# Boost_Converter_1.net
KiCad netlist of a schematic drawn in Altium Designer
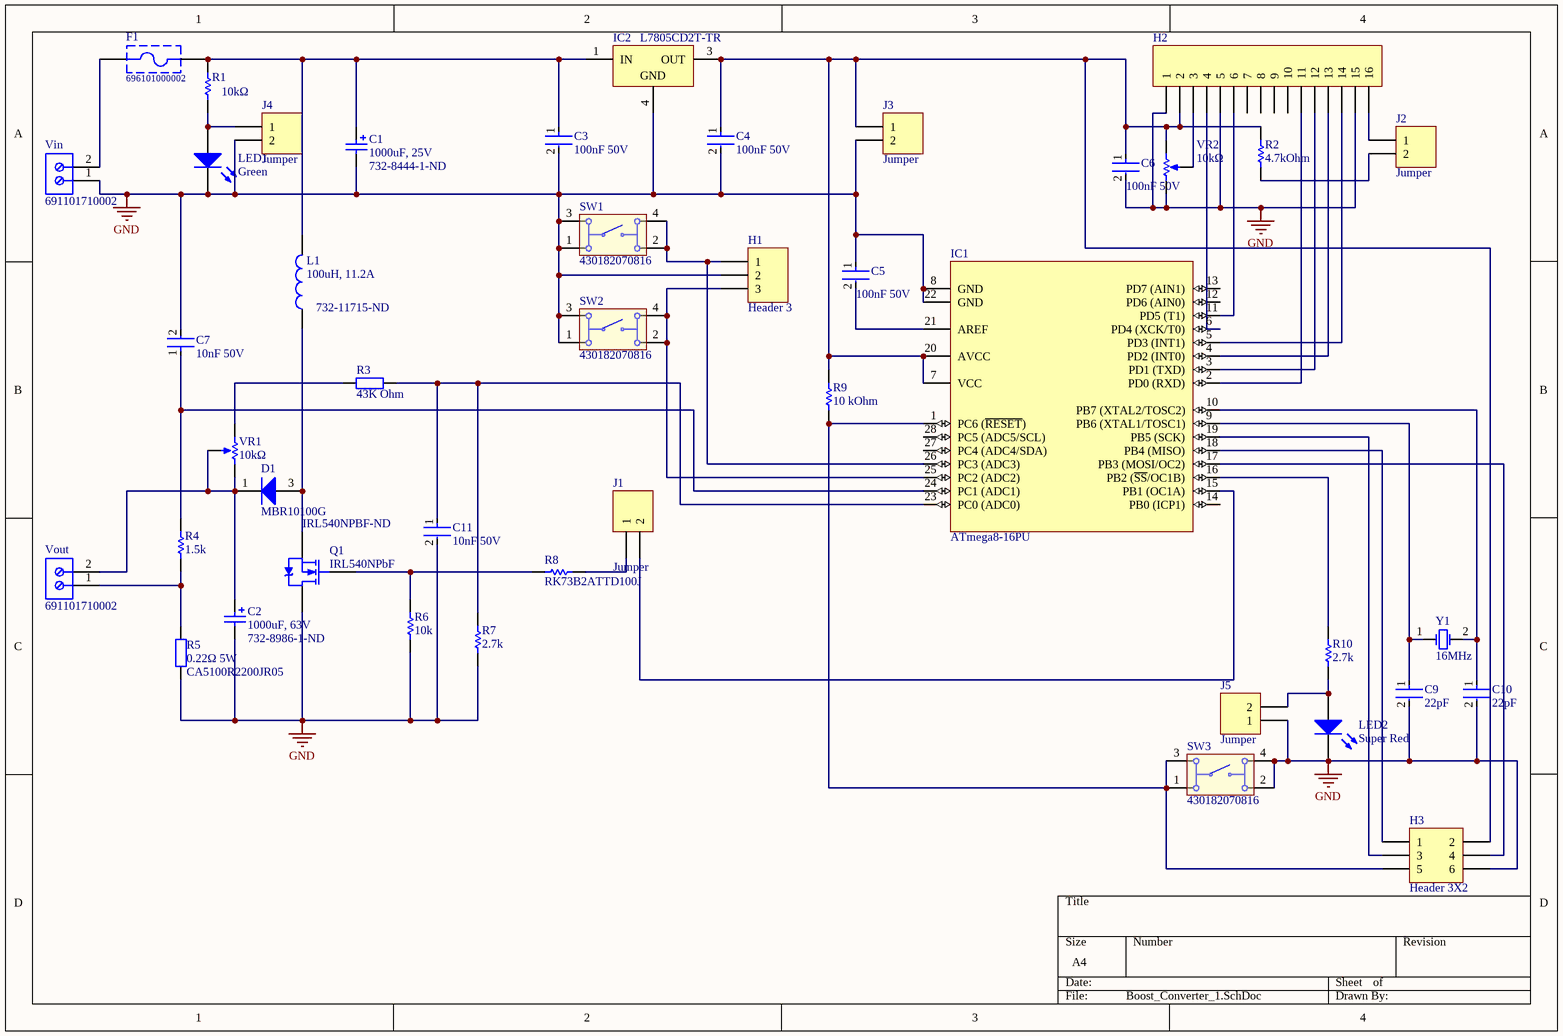
[diagram p0: Boost_Converter_1.SchDoc]

(export (version "E")
  (design (tool "Eeschema 10.0.6"))
  (components
    (comp (ref "C1")
      (value "1000uF, 25V")
      (footprint "WCAP-ASLI_D12.5H14")
      (description "WCAP-ASLI Aluminum Electrolytic Capacitor, V-Chip, SMT, D12.5xH14mm, 1000uF, 25V")
      (fields
        (field (name "MANUFACTURER PART NUMBER") "865080462016")
        (field (name "MANUFACTURER") "Wurth Elektronik")
        (field (name "SUPPLIER PART NUMBER 1") "732-8444-1-ND")
      )
      (libsource (lib "Altium_WCAP-ASLI (rev20b)") (part "865080462016"))
    )
    (comp (ref "C2")
      (value "1000uF, 63V")
      (footprint "WCAP-ATG5_D16H31.5")
      (description "CAP ALUM 1000UF 20% 63V RADIAL")
      (fields
        (field (name "MANUFACTURER PART NUMBER") "860020780025")
        (field (name "MANUFACTURER") "Wurth Elektronik")
        (field (name "SUPPLIER PART NUMBER 1") "732-8986-1-ND")
      )
      (libsource (lib "Altium_WCAP-ATG5 (rev20b)") (part "860020780025"))
    )
    (comp (ref "C3")
      (value "100nF 50V")
      (footprint "FP-GCD21B-0_15-IPC_C")
      (description "Chip Multilayer Ceramic Capacitors for Automotive, 0805, 0.10uF, X7R, 15%, 10%, 50V, Grade 1")
      (fields (field (name "TOLERANCE") "10%"))
      (libsource (lib "Altium Content Vault") (part "b4654b650e69147ec39a6b967a45e02"))
    )
    (comp (ref "C4")
      (value "100nF 50V")
      (footprint "FP-GCD21B-0_15-IPC_C")
      (description "Chip Multilayer Ceramic Capacitors for Automotive, 0805, 0.10uF, X7R, 15%, 10%, 50V, Grade 1")
      (fields (field (name "TOLERANCE") "10%"))
      (libsource (lib "Altium Content Vault") (part "b4654b650e69147ec39a6b967a45e02"))
    )
    (comp (ref "C5")
      (value "100nF 50V")
      (footprint "FP-CL31-IPC_C")
      (description "Cap Ceramic 100nF 50V X7R ±10% SMD 1206 +125°C Embossed T/R")
      (fields (field (name "VOLTAGE") "50V") (field (name "TOLERANCE") "10%"))
      (libsource (lib "Altium Content Vault") (part "b4654b650e69147ec39a6b967a45e02"))
    )
    (comp (ref "C6")
      (value "100nF 50V")
      (footprint "FP-CL31-IPC_C")
      (description "Cap Ceramic 100nF 50V X7R ±10% SMD 1206 +125°C Embossed T/R")
      (fields (field (name "VOLTAGE") "50V") (field (name "TOLERANCE") "10%"))
      (libsource (lib "Altium Content Vault") (part "b4654b650e69147ec39a6b967a45e02"))
    )
    (comp (ref "C7")
      (value "10nF 50V")
      (footprint "FP-CL21-IPC_C")
      (description "CL21 Series 0805 10nF 50V ±10% Tolerance X7R Multilayer Ceramic Chip Capacitor")
      (fields (field (name "TOLERANCE") "10%"))
      (libsource (lib "Altium Content Vault") (part "b4654b650e69147ec39a6b967a45e02"))
    )
    (comp (ref "C9")
      (value "22pF")
      (footprint "FP-C0805C-DN-MFG")
      (description "CAP CER 22PF 50V C0G/NP0 0805")
      (fields
        (field (name "OCTOPART") "https://octopart.com/c0805c220j5gac7210-kemet-3882539")
        (field (name "MANUFACTURER PART NUMBER") "C0805C220J5GAC7210")
      )
      (libsource (lib "Altium Content Vault") (part "b4654b650e69147ec39a6b967a45e02"))
    )
    (comp (ref "C10")
      (value "22pF")
      (footprint "FP-C0805C-DN-MFG")
      (description "CAP CER 22PF 50V C0G/NP0 0805")
      (fields
        (field (name "OCTOPART") "https://octopart.com/c0805c220j5gac7210-kemet-3882539")
        (field (name "MANUFACTURER PART NUMBER") "C0805C220J5GAC7210")
      )
      (libsource (lib "Altium Content Vault") (part "b4654b650e69147ec39a6b967a45e02"))
    )
    (comp (ref "C11")
      (value "10nF 50V")
      (footprint "FP-CL21-IPC_C")
      (description "CL21 Series 0805 10nF 50V ±10% Tolerance X7R Multilayer Ceramic Chip Capacitor")
      (fields (field (name "TOLERANCE") "10%"))
      (libsource (lib "Altium Content Vault") (part "b4654b650e69147ec39a6b967a45e02"))
    )
    (comp (ref "D1")
      (value "MBR10100G")
      (footprint "ONSC-TO-220-2-221B-04_E")
      (description "SWITCHMODE(TM) Power Rectifier, 2-Pin TO-220, Pb-Free, Tube")
      (fields (field (name "MANUFACTURER") "On Semiconductor"))
      (libsource (lib "Altium Content Vault") (part "ONSC-D-K1A3-2_A"))
    )
    (comp (ref "F1")
      (value "696101000002")
      (footprint "696101000002")
      (description "WR-FSH Fuse Holder Blocks Fuse Holder Blocks Clip Cover for PCB")
      (fields (field (name "PUBLISHER") "Wurth Elektronik"))
      (libsource (lib "Altium_WR-FSH (rev18a)") (part "696101000002"))
    )
    (comp (ref "H1")
      (value "Header 3")
      (footprint "HDR1X3")
      (description "Header, 3-Pin")
      (fields (field (name "PUBLISHER") "Altium Limited"))
      (libsource (lib "Miscellaneous Connectors") (part "Header 3"))
    )
    (comp (ref "H2")
      (value "Header 16")
      (footprint "HDR1X16")
      (description "Header, 16-Pin")
      (fields (field (name "PUBLISHER") "Altium Limited"))
      (libsource (lib "Miscellaneous Connectors") (part "Header 16"))
    )
    (comp (ref "H3")
      (value "Header 3X2")
      (footprint "HDR2X3")
      (description "Header, 3-Pin, Dual row")
      (fields (field (name "PUBLISHER") "Altium Limited"))
      (libsource (lib "Miscellaneous Connectors") (part "Header 3X2"))
    )
    (comp (ref "IC1")
      (value "ATmega8-16PU")
      (footprint "28P3")
      (libsource (lib "Altium Content Vault") (part "MC-8B-AT8L-IL28"))
    )
    (comp (ref "IC2")
      (value "L7805CD2T-TR")
      (footprint "TO-263_M")
      (description "Positive Voltage Regulator, 3-Pin D2PAK, Tape and Reel")
      (libsource (lib "Altium Content Vault") (part "PM-REG-L4940-SOT3"))
    )
    (comp (ref "J1")
      (value "Jumper")
      (footprint "HDR1X2H")
      (description "Header, 2-Pin, Right Angle")
      (fields (field (name "PUBLISHER") "Altium Limited"))
      (libsource (lib "") (part "Header 2H_1"))
    )
    (comp (ref "J2")
      (value "Jumper")
      (footprint "HDR1X2H")
      (description "Header, 2-Pin, Right Angle")
      (fields (field (name "PUBLISHER") "Altium Limited"))
      (libsource (lib "Miscellaneous Connectors") (part "Header 2H"))
    )
    (comp (ref "J3")
      (value "Jumper")
      (footprint "HDR1X2H")
      (description "Header, 2-Pin, Right Angle")
      (fields (field (name "PUBLISHER") "Altium Limited"))
      (libsource (lib "Schakeling") (part "Header 2H"))
    )
    (comp (ref "J4")
      (value "Jumper")
      (footprint "HDR1X2H")
      (description "Header, 2-Pin, Right Angle")
      (fields (field (name "PUBLISHER") "Altium Limited"))
      (libsource (lib "Schakeling") (part "Header 2H"))
    )
    (comp (ref "J5")
      (value "Jumper")
      (footprint "HDR1X2H")
      (description "Header, 2-Pin, Right Angle")
      (fields (field (name "PUBLISHER") "Altium Limited"))
      (libsource (lib "") (part "Header 2H_1"))
    )
    (comp (ref "L1")
      (value "100uH, 11.2A")
      (footprint "WE-HCF_2920")
      (description "WE-HCF SMT High Current Inductor, size 2920, 100uH, 11.2A, 25.19mOhm")
      (fields
        (field (name "MANUFACTURER") "Wurth Elektronik")
        (field (name "MANUFACTURER PART NUMBER") "74437529203101")
        (field (name "SUPPLIER PART NUMBER 1") "732-11715-ND")
      )
      (libsource (lib "WE-HCF (rev20c)") (part "74437529203101"))
    )
    (comp (ref "LED1")
      (value "Green")
      (footprint "0805_A")
      (description "SMD mono-color Chip LED, WL-SMCW, Green")
      (fields (field (name "PARTNUMBER") "150080GS75000") (field (name "MANUFACTURER") "Wuerth Elektronik"))
      (libsource (lib "Altium Content Vault") (part "WE-LED_K1A2-2"))
    )
    (comp (ref "LED2")
      (value "Super Red")
      (footprint "0805_A")
      (description "SMD mono-color Chip LED, WL-SMCW, Super Red")
      (fields (field (name "MANUFACTURER") "Wuerth Elektronik") (field (name "PARTNUMBER") "150080SS75000"))
      (libsource (lib "Altium Content Vault") (part "WE-LED_K1A2-2"))
    )
    (comp (ref "Q1")
      (value "IRL540NPbF")
      (footprint "TO-220AB")
      (description "Trans MOSFET N-CH 100V 36A 3-Pin(3+Tab) TO-220AB")
      (fields
        (field (name "SUPPLIER PART NUMBER 1") "IRL540NPBF-ND")
        (field (name "MANUFACTURER") "International Rectifier")
        (field (name "MANUFACTURER PART NUMBER") "IRL540NPBF")
        (field (name "PUBLISHER") "Altium Limited")
      )
      (libsource (lib "Miscellaneous Devices") (part "NMOS-2"))
    )
    (comp (ref "R1")
      (value "10kΩ")
      (footprint "RESC2013X60X35NL10T20")
      (description "Chip Resistor, 10 KOhm, +/- 1%, 0.125 W, -55 to 155 degC, 0805 (2012 Metric), RoHS, Tape and Reel")
      (fields (field (name "MANUFACTURER") "Yageo"))
      (libsource (lib "Altium Content Vault") (part "RES-2"))
    )
    (comp (ref "R2")
      (value "4.7kOhm")
      (footprint "RESC2013X60X40ML20T25")
      (fields (field (name "PART NUMBER") "ERA6AEB472V") (field (name "MANUFACTURER") "Panasonic"))
      (libsource (lib "Altium Content Vault") (part "RES"))
    )
    (comp (ref "R3")
      (value "43K Ohm")
      (footprint "AXIAL-0.4")
      (description "Res Metal Film 43K Ohm 1% 0.6W ±50ppm/C Conformal Coated AXL Ammo")
      (fields
        (field (name "MANUFACTURER") "Yageo")
        (field (name "MANUFACTURER PART NUMBER") "MF0207FTE52-43K")
        (field (name "PUBLISHER") "Altium Limited")
      )
      (libsource (lib "Miscellaneous Devices") (part "Res2"))
    )
    (comp (ref "R4")
      (value "1.5k")
      (footprint "RESC2013X60X35LL10T20")
      (fields (field (name "PART NUMBER") "RC0805JR-131K5L") (field (name "MANUFACTURER") "Yageo"))
      (libsource (lib "Altium Content Vault") (part "RES"))
    )
    (comp (ref "R5")
      (value "0.22Ω 5W")
      (footprint "AXIAL-0.7")
      (description "Resistor")
      (fields
        (field (name "SUPPLIER PART NUMBER 1") "CA5100R2200JR05")
        (field (name "PUBLISHER") "Altium Limited")
      )
      (libsource (lib "") (part "Res2_1"))
    )
    (comp (ref "R6")
      (value "10k")
      (footprint "RESC2013X60X35NL10T20")
      (description "Chip Resistor, 10 KOhm, +/- 1%, 0.125 W, -55 to 155 degC, 0805 (2012 Metric), RoHS, Tape and Reel")
      (fields (field (name "MANUFACTURER") "Yageo"))
      (libsource (lib "Altium Content Vault") (part "RES-2"))
    )
    (comp (ref "R7")
      (value "2.7k")
      (footprint "RESC2013X50X30NL20T20")
      (fields (field (name "PART NUMBER") "CRCW08052K70JNEA") (field (name "MANUFACTURER") "Vishay Dale"))
      (libsource (lib "Altium Content Vault") (part "RES"))
    )
    (comp (ref "R8")
      (value "RK73B2ATTD100J")
      (footprint "RESC2013X60X30ML20T20")
      (fields (field (name "MANUFACTURER") "KOA Speer"))
      (libsource (lib "Altium Content Vault") (part "RES"))
    )
    (comp (ref "R9")
      (value "10 kOhm")
      (footprint "RESC2013X60X35NL10T20")
      (description "Chip Resistor, 10 KOhm, +/- 1%, 0.125 W, -55 to 155 degC, 0805 (2012 Metric), RoHS, Tape and Reel")
      (fields (field (name "MANUFACTURER") "Yageo"))
      (libsource (lib "Altium Content Vault") (part "RES-2"))
    )
    (comp (ref "R10")
      (value "2.7k")
      (footprint "RESC2013X50X30NL20T20")
      (fields (field (name "PART NUMBER") "CRCW08052K70JNEA") (field (name "MANUFACTURER") "Vishay Dale"))
      (libsource (lib "Altium Content Vault") (part "RES"))
    )
    (comp (ref "SW1")
      (value "430182070816")
      (footprint "430182070816")
      (description "WS-TASV SMD Tact Switch 6X6 mm")
      (fields (field (name "MANUFACTURER") "Wuerth Elektronik"))
      (libsource (lib "Altium Content Vault") (part "WE-TACT-SW-4"))
    )
    (comp (ref "SW2")
      (value "430182070816")
      (footprint "430182070816")
      (description "WS-TASV SMD Tact Switch 6X6 mm")
      (fields (field (name "MANUFACTURER") "Wuerth Elektronik"))
      (libsource (lib "Altium Content Vault") (part "WE-TACT-SW-4"))
    )
    (comp (ref "SW3")
      (value "430182070816")
      (footprint "430182070816")
      (description "WS-TASV SMD Tact Switch 6X6 mm")
      (fields (field (name "MANUFACTURER") "Wuerth Elektronik"))
      (libsource (lib "Altium Content Vault") (part "WE-TACT-SW-4"))
    )
    (comp (ref "Vin")
      (value "691101710002")
      (footprint "691101710002")
      (description "Series 101 - 5.00 mm Horizontal Entry Modular with Pressure Clamp WR-TBL, 2 pin")
      (fields (field (name "MANUFACTURER") "Wurth Elektronik") (field (name "PUBLISHER") "WurthElektronik"))
      (libsource (lib "Altium Content Vault") (part "WE-CN-1P-F-TB2"))
    )
    (comp (ref "Vout")
      (value "691101710002")
      (footprint "691101710002")
      (description "Series 101 - 5.00 mm Horizontal Entry Modular with Pressure Clamp WR-TBL, 2 pin")
      (fields (field (name "MANUFACTURER") "Wurth Elektronik") (field (name "PUBLISHER") "WurthElektronik"))
      (libsource (lib "Altium Content Vault") (part "WE-CN-1P-F-TB2"))
    )
    (comp (ref "VR1")
      (value "10kΩ")
      (footprint "10k_trimmer")
      (description "Square Trimming Potentiometer, 10 KOhm, 500 mW, -55 to 125 degC, 3-Pin THD, RoHS, Tube")
      (fields (field (name "TOLERANCE") "10%") (field (name "MANUFACTURER") "Bourns"))
      (libsource (lib "Schakeling") (part "CMP-2000-05078-1"))
    )
    (comp (ref "VR2")
      (value "10kΩ")
      (footprint "10k_trimmer")
      (description "Square Trimming Potentiometer, 10 KOhm, 500 mW, -55 to 125 degC, 3-Pin THD, RoHS, Tube")
      (fields (field (name "TOLERANCE") "10%") (field (name "MANUFACTURER") "Bourns"))
      (libsource (lib "Schakeling") (part "CMP-2000-05078-1"))
    )
    (comp (ref "Y1")
      (value "16MHz")
      (footprint "WE-XTAL_HC49/4HSMX")
      (description "WE-XTAL Quartz Crystal, SMT, HC49/4HSMX, 16MHz, +/-30ppm")
      (fields
        (field (name "MANUFACTURER PART NUMBER") "830051235")
        (field (name "MANUFACTURER") "Wurth Elektronik")
      )
      (libsource (lib "Altium_WE-XTAL (rev20c)") (part "830051235"))
    )
  )
  (nets
    (net (code "1") (name "GND") (class "Default")
      (node (ref "C1") (pin "2") (pinfunction "N_2") (pintype "passive"))
      (node (ref "C10") (pin "2") (pinfunction "2_2") (pintype "passive"))
      (node (ref "C11") (pin "2") (pinfunction "2_2") (pintype "passive"))
      (node (ref "C2") (pin "2") (pinfunction "N_2") (pintype "passive"))
      (node (ref "C3") (pin "2") (pinfunction "2_2") (pintype "passive"))
      (node (ref "C4") (pin "2") (pinfunction "2_2") (pintype "passive"))
      (node (ref "C5") (pin "1") (pinfunction "1_1") (pintype "passive"))
      (node (ref "C6") (pin "2") (pinfunction "2_2") (pintype "passive"))
      (node (ref "C7") (pin "2") (pinfunction "2_2") (pintype "passive"))
      (node (ref "C9") (pin "2") (pinfunction "2_2") (pintype "passive"))
      (node (ref "H1") (pin "2") (pinfunction "2_2") (pintype "passive"))
      (node (ref "H2") (pin "1") (pinfunction "1_1") (pintype "passive"))
      (node (ref "H2") (pin "15") (pinfunction "15_15") (pintype "passive"))
      (node (ref "H2") (pin "5") (pinfunction "5_5") (pintype "passive"))
      (node (ref "H3") (pin "6") (pinfunction "6_6") (pintype "passive"))
      (node (ref "IC1") (pin "22") (pinfunction "GND_22") (pintype "power_in"))
      (node (ref "IC1") (pin "8") (pinfunction "GND_8") (pintype "power_in"))
      (node (ref "IC2") (pin "4") (pinfunction "GND_4") (pintype "power_in"))
      (node (ref "J3") (pin "2") (pinfunction "2_2") (pintype "passive"))
      (node (ref "J4") (pin "2") (pinfunction "2_2") (pintype "passive"))
      (node (ref "J5") (pin "1") (pinfunction "1_1") (pintype "passive"))
      (node (ref "LED1") (pin "1") (pinfunction "K_1") (pintype "passive"))
      (node (ref "LED2") (pin "1") (pinfunction "K_1") (pintype "passive"))
      (node (ref "Q1") (pin "2") (pinfunction "D_2") (pintype "passive"))
      (node (ref "R5") (pin "1") (pinfunction "1_1") (pintype "passive"))
      (node (ref "R6") (pin "1") (pinfunction "1_1") (pintype "passive"))
      (node (ref "R7") (pin "1") (pinfunction "1_1") (pintype "passive"))
      (node (ref "SW1") (pin "1") (pinfunction "1_1") (pintype "passive"))
      (node (ref "SW1") (pin "3") (pinfunction "3_3") (pintype "passive"))
      (node (ref "SW2") (pin "1") (pinfunction "1_1") (pintype "passive"))
      (node (ref "SW2") (pin "3") (pinfunction "3_3") (pintype "passive"))
      (node (ref "SW3") (pin "2") (pinfunction "2_2") (pintype "passive"))
      (node (ref "SW3") (pin "4") (pinfunction "4_4") (pintype "passive"))
      (node (ref "VR2") (pin "3") (pinfunction "CW_3") (pintype "passive"))
      (node (ref "Vin") (pin "1") (pinfunction "1_1") (pintype "passive"))
    )
    (net (code "2") (name "Net-(C1-P)") (class "Default")
      (node (ref "C1") (pin "1") (pinfunction "P_1") (pintype "passive"))
      (node (ref "C3") (pin "1") (pinfunction "1_1") (pintype "passive"))
      (node (ref "F1") (pin "2") (pinfunction "2_2") (pintype "passive"))
      (node (ref "IC2") (pin "1") (pinfunction "IN_1") (pintype "power_in"))
      (node (ref "L1") (pin "2") (pinfunction "2_2") (pintype "passive"))
      (node (ref "R1") (pin "2") (pinfunction "2_2") (pintype "passive"))
    )
    (net (code "3") (name "Net-(C2-P)") (class "Default")
      (node (ref "C2") (pin "1") (pinfunction "P_1") (pintype "passive"))
      (node (ref "D1") (pin "1") (pinfunction "K_1") (pintype "passive"))
      (node (ref "VR1") (pin "1") (pinfunction "CCW_1") (pintype "passive"))
      (node (ref "VR1") (pin "2") (pinfunction "WIPER_2") (pintype "passive"))
      (node (ref "Vout") (pin "2") (pinfunction "2_2") (pintype "passive"))
    )
    (net (code "4") (name "Net-(D1-A)") (class "Default")
      (node (ref "D1") (pin "3") (pinfunction "A_3") (pintype "passive"))
      (node (ref "L1") (pin "1") (pinfunction "1_1") (pintype "passive"))
      (node (ref "Q1") (pin "3") (pinfunction "S_3") (pintype "passive"))
    )
    (net (code "5") (name "Net-(F1-Pad1)") (class "Default")
      (node (ref "F1") (pin "1") (pinfunction "1_1") (pintype "passive"))
      (node (ref "Vin") (pin "2") (pinfunction "2_2") (pintype "passive"))
    )
    (net (code "6") (name "Net-(H2-Pad16)") (class "Default")
      (node (ref "H2") (pin "16") (pinfunction "16_16") (pintype "passive"))
      (node (ref "J2") (pin "1") (pinfunction "1_1") (pintype "passive"))
    )
    (net (code "7") (name "Net-(IC1-AREF)") (class "Default")
      (node (ref "C5") (pin "2") (pinfunction "2_2") (pintype "passive"))
      (node (ref "IC1") (pin "21") (pinfunction "AREF_21") (pintype "passive"))
    )
    (net (code "8") (name "Net-(IC1-AVCC)") (class "Default")
      (node (ref "C4") (pin "1") (pinfunction "1_1") (pintype "passive"))
      (node (ref "C6") (pin "1") (pinfunction "1_1") (pintype "passive"))
      (node (ref "H2") (pin "2") (pinfunction "2_2") (pintype "passive"))
      (node (ref "H3") (pin "2") (pinfunction "2_2") (pintype "passive"))
      (node (ref "IC1") (pin "20") (pinfunction "AVCC_20") (pintype "power_in"))
      (node (ref "IC1") (pin "7") (pinfunction "VCC_7") (pintype "power_in"))
      (node (ref "IC2") (pin "3") (pinfunction "OUT_3") (pintype "power_in"))
      (node (ref "J3") (pin "1") (pinfunction "1_1") (pintype "passive"))
      (node (ref "R2") (pin "2") (pinfunction "2_2") (pintype "passive"))
      (node (ref "R9") (pin "2") (pinfunction "2_2") (pintype "passive"))
      (node (ref "VR2") (pin "1") (pinfunction "CCW_1") (pintype "passive"))
    )
    (net (code "9") (name "Net-(IC1-PB1_(OC1A))") (class "Default")
      (node (ref "IC1") (pin "15") (pinfunction "PB1_(OC1A)_15") (pintype "bidirectional"))
      (node (ref "J1") (pin "2") (pinfunction "2_2") (pintype "passive"))
    )
    (net (code "10") (name "Net-(IC1-PB2_(~{SS}{slash}OC1B))") (class "Default")
      (node (ref "IC1") (pin "16") (pinfunction "PB2_(~{SS}/OC1B)_16") (pintype "bidirectional"))
      (node (ref "R10") (pin "2") (pinfunction "2_2") (pintype "passive"))
    )
    (net (code "11") (name "Net-(IC1-PB3_(MOSI{slash}OC2))") (class "Default")
      (node (ref "H3") (pin "4") (pinfunction "4_4") (pintype "passive"))
      (node (ref "IC1") (pin "17") (pinfunction "PB3_(MOSI/OC2)_17") (pintype "bidirectional"))
    )
    (net (code "12") (name "Net-(IC1-PB4_(MISO))") (class "Default")
      (node (ref "H3") (pin "1") (pinfunction "1_1") (pintype "passive"))
      (node (ref "IC1") (pin "18") (pinfunction "PB4_(MISO)_18") (pintype "bidirectional"))
    )
    (net (code "13") (name "Net-(IC1-PB5_(SCK))") (class "Default")
      (node (ref "H3") (pin "3") (pinfunction "3_3") (pintype "passive"))
      (node (ref "IC1") (pin "19") (pinfunction "PB5_(SCK)_19") (pintype "bidirectional"))
    )
    (net (code "14") (name "Net-(IC1-PB6_(XTAL1{slash}TOSC1))") (class "Default")
      (node (ref "C9") (pin "1") (pinfunction "1_1") (pintype "passive"))
      (node (ref "IC1") (pin "9") (pinfunction "PB6_(XTAL1/TOSC1)_9") (pintype "bidirectional"))
      (node (ref "Y1") (pin "1") (pinfunction "OSC1_1") (pintype "passive"))
    )
    (net (code "15") (name "Net-(IC1-PB7_(XTAL2{slash}TOSC2))") (class "Default")
      (node (ref "C10") (pin "1") (pinfunction "1_1") (pintype "passive"))
      (node (ref "IC1") (pin "10") (pinfunction "PB7_(XTAL2/TOSC2)_10") (pintype "bidirectional"))
      (node (ref "Y1") (pin "2") (pinfunction "OSC2_2") (pintype "passive"))
    )
    (net (code "16") (name "Net-(IC1-PC0_(ADC0))") (class "Default")
      (node (ref "C11") (pin "1") (pinfunction "1_1") (pintype "passive"))
      (node (ref "IC1") (pin "23") (pinfunction "PC0_(ADC0)_23") (pintype "bidirectional"))
      (node (ref "R3") (pin "2") (pinfunction "2_2") (pintype "passive"))
      (node (ref "R7") (pin "2") (pinfunction "2_2") (pintype "passive"))
    )
    (net (code "17") (name "Net-(IC1-PC1_(ADC1))") (class "Default")
      (node (ref "C7") (pin "1") (pinfunction "1_1") (pintype "passive"))
      (node (ref "IC1") (pin "24") (pinfunction "PC1_(ADC1)_24") (pintype "bidirectional"))
      (node (ref "R4") (pin "2") (pinfunction "2_2") (pintype "passive"))
    )
    (net (code "18") (name "Net-(IC1-PC2_(ADC2))") (class "Default")
      (node (ref "H1") (pin "3") (pinfunction "3_3") (pintype "passive"))
      (node (ref "IC1") (pin "25") (pinfunction "PC2_(ADC2)_25") (pintype "bidirectional"))
      (node (ref "SW2") (pin "2") (pinfunction "2_2") (pintype "passive"))
      (node (ref "SW2") (pin "4") (pinfunction "4_4") (pintype "passive"))
    )
    (net (code "19") (name "Net-(IC1-PC3_(ADC3))") (class "Default")
      (node (ref "H1") (pin "1") (pinfunction "1_1") (pintype "passive"))
      (node (ref "IC1") (pin "26") (pinfunction "PC3_(ADC3)_26") (pintype "bidirectional"))
      (node (ref "SW1") (pin "2") (pinfunction "2_2") (pintype "passive"))
      (node (ref "SW1") (pin "4") (pinfunction "4_4") (pintype "passive"))
    )
    (net (code "20") (name "Net-(IC1-PC6_(~{RESET}))") (class "Default")
      (node (ref "H3") (pin "5") (pinfunction "5_5") (pintype "passive"))
      (node (ref "IC1") (pin "1") (pinfunction "PC6_(~{RESET})_1") (pintype "bidirectional"))
      (node (ref "R9") (pin "1") (pinfunction "1_1") (pintype "passive"))
      (node (ref "SW3") (pin "1") (pinfunction "1_1") (pintype "passive"))
      (node (ref "SW3") (pin "3") (pinfunction "3_3") (pintype "passive"))
    )
    (net (code "21") (name "Net-(IC1-PD0_(RXD))") (class "Default")
      (node (ref "H2") (pin "11") (pinfunction "11_11") (pintype "passive"))
      (node (ref "IC1") (pin "2") (pinfunction "PD0_(RXD)_2") (pintype "bidirectional"))
    )
    (net (code "22") (name "Net-(IC1-PD1_(TXD))") (class "Default")
      (node (ref "H2") (pin "12") (pinfunction "12_12") (pintype "passive"))
      (node (ref "IC1") (pin "3") (pinfunction "PD1_(TXD)_3") (pintype "bidirectional"))
    )
    (net (code "23") (name "Net-(IC1-PD2_(INT0))") (class "Default")
      (node (ref "H2") (pin "13") (pinfunction "13_13") (pintype "passive"))
      (node (ref "IC1") (pin "4") (pinfunction "PD2_(INT0)_4") (pintype "bidirectional"))
    )
    (net (code "24") (name "Net-(IC1-PD3_(INT1))") (class "Default")
      (node (ref "H2") (pin "14") (pinfunction "14_14") (pintype "passive"))
      (node (ref "IC1") (pin "5") (pinfunction "PD3_(INT1)_5") (pintype "bidirectional"))
    )
    (net (code "25") (name "Net-(IC1-PD4_(XCK{slash}T0))") (class "Default")
      (node (ref "H2") (pin "4") (pinfunction "4_4") (pintype "passive"))
      (node (ref "IC1") (pin "6") (pinfunction "PD4_(XCK/T0)_6") (pintype "bidirectional"))
    )
    (net (code "26") (name "Net-(IC1-PD5_(T1))") (class "Default")
      (node (ref "H2") (pin "6") (pinfunction "6_6") (pintype "passive"))
      (node (ref "IC1") (pin "11") (pinfunction "PD5_(T1)_11") (pintype "bidirectional"))
    )
    (net (code "27") (name "Net-(J1-Pad1)") (class "Default")
      (node (ref "J1") (pin "1") (pinfunction "1_1") (pintype "passive"))
      (node (ref "R8") (pin "2") (pinfunction "2_2") (pintype "passive"))
    )
    (net (code "28") (name "Net-(J2-Pad2)") (class "Default")
      (node (ref "J2") (pin "2") (pinfunction "2_2") (pintype "passive"))
      (node (ref "R2") (pin "1") (pinfunction "1_1") (pintype "passive"))
    )
    (net (code "29") (name "Net-(LED1-A)") (class "Default")
      (node (ref "J4") (pin "1") (pinfunction "1_1") (pintype "passive"))
      (node (ref "LED1") (pin "2") (pinfunction "A_2") (pintype "passive"))
      (node (ref "R1") (pin "1") (pinfunction "1_1") (pintype "passive"))
    )
    (net (code "30") (name "Net-(LED2-A)") (class "Default")
      (node (ref "J5") (pin "2") (pinfunction "2_2") (pintype "passive"))
      (node (ref "LED2") (pin "2") (pinfunction "A_2") (pintype "passive"))
      (node (ref "R10") (pin "1") (pinfunction "1_1") (pintype "passive"))
    )
    (net (code "31") (name "Net-(Q1-G)") (class "Default")
      (node (ref "Q1") (pin "1") (pinfunction "G_1") (pintype "passive"))
      (node (ref "R6") (pin "2") (pinfunction "2_2") (pintype "passive"))
      (node (ref "R8") (pin "1") (pinfunction "1_1") (pintype "passive"))
    )
    (net (code "32") (name "Net-(R4-Pad1)") (class "Default")
      (node (ref "R4") (pin "1") (pinfunction "1_1") (pintype "passive"))
      (node (ref "R5") (pin "2") (pinfunction "2_2") (pintype "passive"))
      (node (ref "Vout") (pin "1") (pinfunction "1_1") (pintype "passive"))
    )
    (net (code "33") (name "Net-(VR1-CW)") (class "Default")
      (node (ref "R3") (pin "1") (pinfunction "1_1") (pintype "passive"))
      (node (ref "VR1") (pin "3") (pinfunction "CW_3") (pintype "passive"))
    )
    (net (code "34") (name "Net-(VR2-WIPER)") (class "Default")
      (node (ref "H2") (pin "3") (pinfunction "3_3") (pintype "passive"))
      (node (ref "VR2") (pin "2") (pinfunction "WIPER_2") (pintype "passive"))
    )
    (net (code "35") (name "unconnected-(H2-Pad7)") (class "Default")
      (node (ref "H2") (pin "7") (pinfunction "7_7") (pintype "passive"))
    )
    (net (code "36") (name "unconnected-(H2-Pad8)") (class "Default")
      (node (ref "H2") (pin "8") (pinfunction "8_8") (pintype "passive"))
    )
    (net (code "37") (name "unconnected-(H2-Pad9)") (class "Default")
      (node (ref "H2") (pin "9") (pinfunction "9_9") (pintype "passive"))
    )
    (net (code "38") (name "unconnected-(H2-Pad10)") (class "Default")
      (node (ref "H2") (pin "10") (pinfunction "10_10") (pintype "passive"))
    )
    (net (code "39") (name "unconnected-(IC1-PB0_(ICP1)-Pad14)") (class "Default")
      (node (ref "IC1") (pin "14") (pinfunction "PB0_(ICP1)_14") (pintype "bidirectional"))
    )
    (net (code "40") (name "unconnected-(IC1-PC4_(ADC4{slash}SDA)-Pad27)") (class "Default")
      (node (ref "IC1") (pin "27") (pinfunction "PC4_(ADC4/SDA)_27") (pintype "bidirectional"))
    )
    (net (code "41") (name "unconnected-(IC1-PC5_(ADC5{slash}SCL)-Pad28)") (class "Default")
      (node (ref "IC1") (pin "28") (pinfunction "PC5_(ADC5/SCL)_28") (pintype "bidirectional"))
    )
    (net (code "42") (name "unconnected-(IC1-PD6_(AIN0)-Pad12)") (class "Default")
      (node (ref "IC1") (pin "12") (pinfunction "PD6_(AIN0)_12") (pintype "bidirectional"))
    )
    (net (code "43") (name "unconnected-(IC1-PD7_(AIN1)-Pad13)") (class "Default")
      (node (ref "IC1") (pin "13") (pinfunction "PD7_(AIN1)_13") (pintype "bidirectional"))
    )
  )
)
